# eva01_connectors.net
KiCad netlist of a schematic drawn in Altium Designer
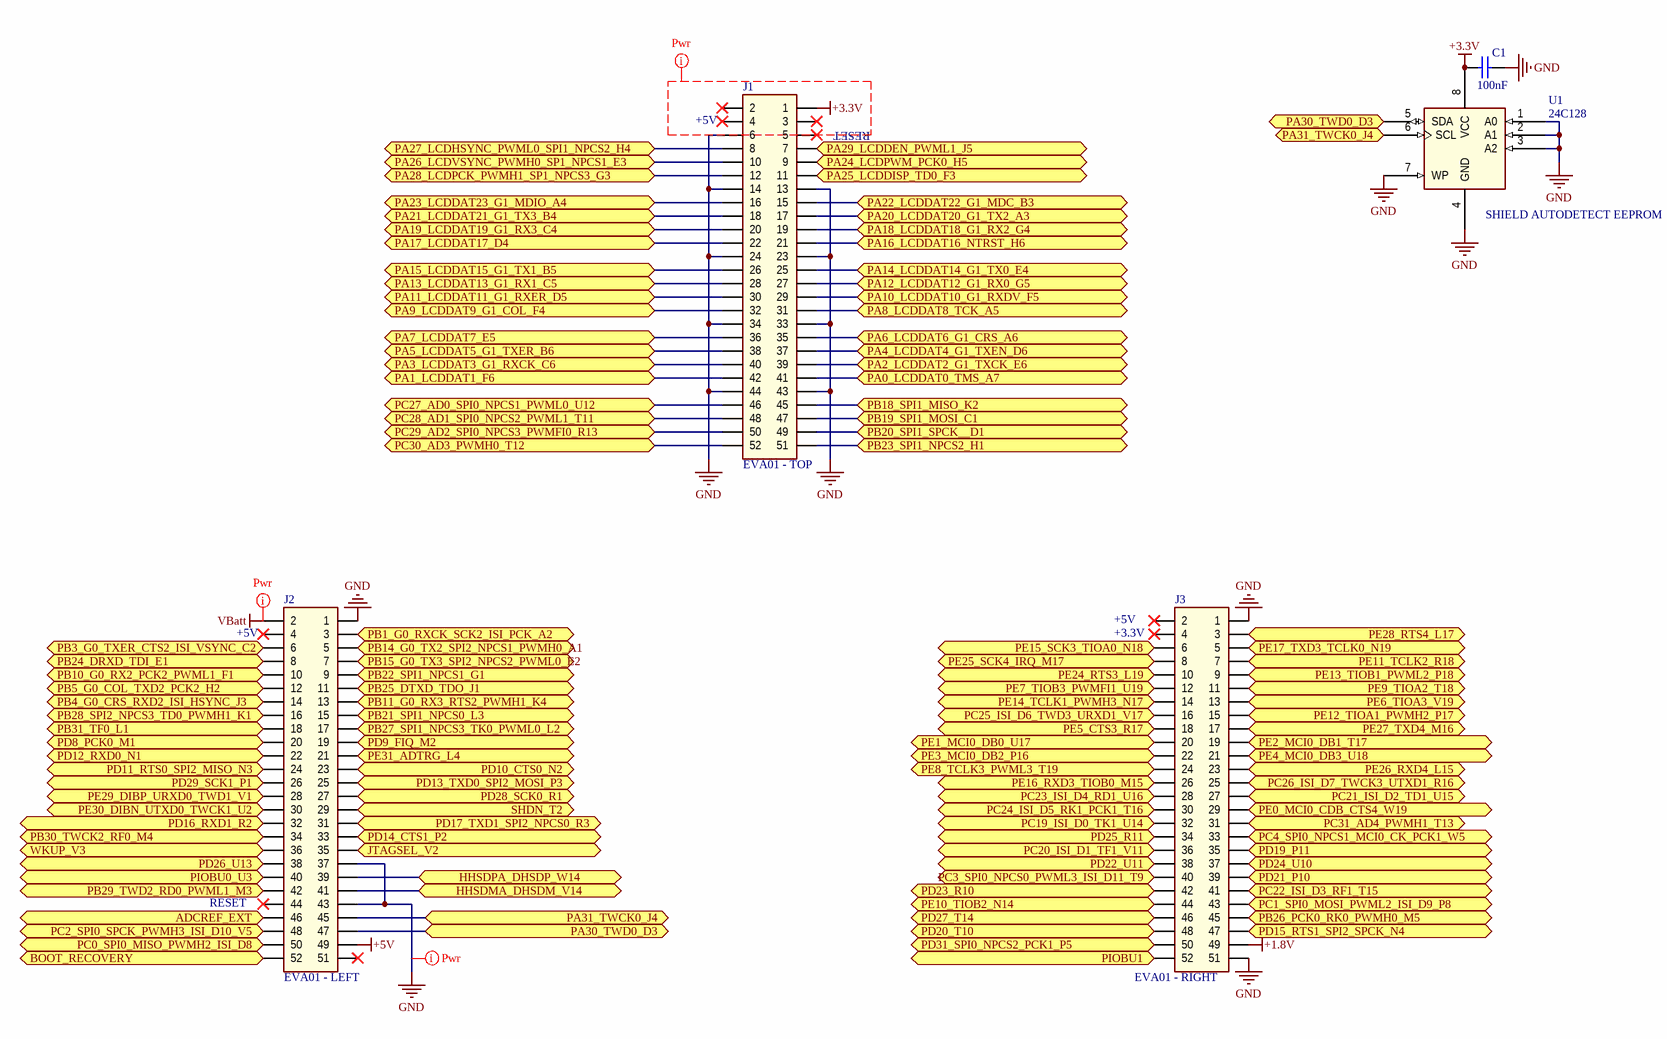
[diagram p0: eva01_connectors.SchDoc]

(export (version "E")
  (design (tool "Eeschema 10.0.6"))
  (components
    (comp (ref "C1")
      (value "100nF")
      (footprint "0603_[1608]")
      (description "Ceramic X7R 50V")
      (fields (field (name "PUBLISHER") "Altium Limited"))
      (libsource (lib "DEVELER_Library") (part "Cap"))
    )
    (comp (ref "J1")
      (value "EVA01 - TOP")
      (footprint "SOCKET_2x26_2.54MM_SMD")
      (description "Socket Header, 26 pin, 13x2, 2.54mm, H=8.5mm")
      (fields (field (name "PART NUMBER") "Tyco 1-1634688"))
      (libsource (lib "DEVELER_Library") (part "Header 26x2"))
    )
    (comp (ref "J2")
      (value "EVA01 - LEFT")
      (footprint "SOCKET_2x26_2.54MM_SMD")
      (description "Pin header 26x2")
      (fields (field (name "PART NUMBER") "Tyco 1-1634688"))
      (libsource (lib "DEVELER_Library") (part "Header 26x2"))
    )
    (comp (ref "J3")
      (value "EVA01 - RIGHT")
      (footprint "SOCKET_2x26_2.54MM_SMD")
      (description "Pin header 26x2")
      (fields (field (name "PART NUMBER") "Tyco 1-1634688"))
      (libsource (lib "DEVELER_Library") (part "Header 26x2"))
    )
    (comp (ref "U1")
      (value "24C128")
      (footprint "SOIC8")
      (description "EEPROM")
      (libsource (lib "DEVELER_Library") (part "EEPROM-SOIC8"))
    )
  )
  (nets
    (net (code "1") (name "+1.8V") (class "Default")
      (node (ref "J3") (pin "49") (pinfunction "49_49") (pintype "passive"))
    )
    (net (code "2") (name "+3.3V") (class "Default")
      (node (ref "C1") (pin "2") (pinfunction "2_2") (pintype "passive"))
      (node (ref "J1") (pin "1") (pinfunction "1_1") (pintype "passive"))
      (node (ref "U1") (pin "8") (pinfunction "VCC_8") (pintype "power_in"))
    )
    (net (code "3") (name "+5V") (class "Default")
      (node (ref "J2") (pin "49") (pinfunction "49_49") (pintype "passive"))
    )
    (net (code "4") (name "/ADCREF_EXT") (class "Default")
      (node (ref "J2") (pin "46") (pinfunction "46_46") (pintype "passive"))
    )
    (net (code "5") (name "/BOOT_RECOVERY") (class "Default")
      (node (ref "J2") (pin "52") (pinfunction "52_52") (pintype "passive"))
    )
    (net (code "6") (name "/HHSDMA_DHSDM_V14") (class "Default")
      (node (ref "J2") (pin "41") (pinfunction "41_41") (pintype "passive"))
    )
    (net (code "7") (name "/HHSDPA_DHSDP_W14") (class "Default")
      (node (ref "J2") (pin "39") (pinfunction "39_39") (pintype "passive"))
    )
    (net (code "8") (name "/JTAGSEL_V2") (class "Default")
      (node (ref "J2") (pin "35") (pinfunction "35_35") (pintype "passive"))
    )
    (net (code "9") (name "/PA0_LCDDAT0_TMS_A7") (class "Default")
      (node (ref "J1") (pin "41") (pinfunction "41_41") (pintype "passive"))
    )
    (net (code "10") (name "/PA1_LCDDAT1_F6") (class "Default")
      (node (ref "J1") (pin "42") (pinfunction "42_42") (pintype "passive"))
    )
    (net (code "11") (name "/PA2_LCDDAT2_G1_TXCK_E6") (class "Default")
      (node (ref "J1") (pin "39") (pinfunction "39_39") (pintype "passive"))
    )
    (net (code "12") (name "/PA3_LCDDAT3_G1_RXCK_C6") (class "Default")
      (node (ref "J1") (pin "40") (pinfunction "40_40") (pintype "passive"))
    )
    (net (code "13") (name "/PA4_LCDDAT4_G1_TXEN_D6") (class "Default")
      (node (ref "J1") (pin "37") (pinfunction "37_37") (pintype "passive"))
    )
    (net (code "14") (name "/PA5_LCDDAT5_G1_TXER_B6") (class "Default")
      (node (ref "J1") (pin "38") (pinfunction "38_38") (pintype "passive"))
    )
    (net (code "15") (name "/PA6_LCDDAT6_G1_CRS_A6") (class "Default")
      (node (ref "J1") (pin "35") (pinfunction "35_35") (pintype "passive"))
    )
    (net (code "16") (name "/PA7_LCDDAT7_E5") (class "Default")
      (node (ref "J1") (pin "36") (pinfunction "36_36") (pintype "passive"))
    )
    (net (code "17") (name "/PA8_LCDDAT8_TCK_A5") (class "Default")
      (node (ref "J1") (pin "31") (pinfunction "31_31") (pintype "passive"))
    )
    (net (code "18") (name "/PA9_LCDDAT9_G1_COL_F4") (class "Default")
      (node (ref "J1") (pin "32") (pinfunction "32_32") (pintype "passive"))
    )
    (net (code "19") (name "/PA10_LCDDAT10_G1_RXDV_F5") (class "Default")
      (node (ref "J1") (pin "29") (pinfunction "29_29") (pintype "passive"))
    )
    (net (code "20") (name "/PA11_LCDDAT11_G1_RXER_D5") (class "Default")
      (node (ref "J1") (pin "30") (pinfunction "30_30") (pintype "passive"))
    )
    (net (code "21") (name "/PA12_LCDDAT12_G1_RX0_G5") (class "Default")
      (node (ref "J1") (pin "27") (pinfunction "27_27") (pintype "passive"))
    )
    (net (code "22") (name "/PA13_LCDDAT13_G1_RX1_C5") (class "Default")
      (node (ref "J1") (pin "28") (pinfunction "28_28") (pintype "passive"))
    )
    (net (code "23") (name "/PA14_LCDDAT14_G1_TX0_E4") (class "Default")
      (node (ref "J1") (pin "25") (pinfunction "25_25") (pintype "passive"))
    )
    (net (code "24") (name "/PA15_LCDDAT15_G1_TX1_B5") (class "Default")
      (node (ref "J1") (pin "26") (pinfunction "26_26") (pintype "passive"))
    )
    (net (code "25") (name "/PA16_LCDDAT16_NTRST_H6") (class "Default")
      (node (ref "J1") (pin "21") (pinfunction "21_21") (pintype "passive"))
    )
    (net (code "26") (name "/PA17_LCDDAT17_D4") (class "Default")
      (node (ref "J1") (pin "22") (pinfunction "22_22") (pintype "passive"))
    )
    (net (code "27") (name "/PA18_LCDDAT18_G1_RX2_G4") (class "Default")
      (node (ref "J1") (pin "19") (pinfunction "19_19") (pintype "passive"))
    )
    (net (code "28") (name "/PA19_LCDDAT19_G1_RX3_C4") (class "Default")
      (node (ref "J1") (pin "20") (pinfunction "20_20") (pintype "passive"))
    )
    (net (code "29") (name "/PA20_LCDDAT20_G1_TX2_A3") (class "Default")
      (node (ref "J1") (pin "17") (pinfunction "17_17") (pintype "passive"))
    )
    (net (code "30") (name "/PA21_LCDDAT21_G1_TX3_B4") (class "Default")
      (node (ref "J1") (pin "18") (pinfunction "18_18") (pintype "passive"))
    )
    (net (code "31") (name "/PA22_LCDDAT22_G1_MDC_B3") (class "Default")
      (node (ref "J1") (pin "15") (pinfunction "15_15") (pintype "passive"))
    )
    (net (code "32") (name "/PA23_LCDDAT23_G1_MDIO_A4") (class "Default")
      (node (ref "J1") (pin "16") (pinfunction "16_16") (pintype "passive"))
    )
    (net (code "33") (name "/PA24_LCDPWM_PCK0_H5") (class "Default")
      (node (ref "J1") (pin "9") (pinfunction "9_9") (pintype "passive"))
    )
    (net (code "34") (name "/PA25_LCDDISP_TD0_F3") (class "Default")
      (node (ref "J1") (pin "11") (pinfunction "11_11") (pintype "passive"))
    )
    (net (code "35") (name "/PA26_LCDVSYNC_PWMH0_SP1_NPCS1_E3") (class "Default")
      (node (ref "J1") (pin "10") (pinfunction "10_10") (pintype "passive"))
    )
    (net (code "36") (name "/PA27_LCDHSYNC_PWML0_SPI1_NPCS2_H4") (class "Default")
      (node (ref "J1") (pin "8") (pinfunction "8_8") (pintype "passive"))
    )
    (net (code "37") (name "/PA28_LCDPCK_PWMH1_SP1_NPCS3_G3") (class "Default")
      (node (ref "J1") (pin "12") (pinfunction "12_12") (pintype "passive"))
    )
    (net (code "38") (name "/PA29_LCDDEN_PWML1_J5") (class "Default")
      (node (ref "J1") (pin "7") (pinfunction "7_7") (pintype "passive"))
    )
    (net (code "39") (name "/PA30_TWD0_D3") (class "Default")
      (node (ref "J2") (pin "47") (pinfunction "47_47") (pintype "passive"))
      (node (ref "U1") (pin "5") (pinfunction "SDA_5") (pintype "bidirectional"))
    )
    (net (code "40") (name "/PA31_TWCK0_J4") (class "Default")
      (node (ref "J2") (pin "45") (pinfunction "45_45") (pintype "passive"))
      (node (ref "U1") (pin "6") (pinfunction "SCL_6") (pintype "input"))
    )
    (net (code "41") (name "/PB1_G0_RXCK_SCK2_ISI_PCK_A2") (class "Default")
      (node (ref "J2") (pin "3") (pinfunction "3_3") (pintype "passive"))
    )
    (net (code "42") (name "/PB3_G0_TXER_CTS2_ISI_VSYNC_C2") (class "Default")
      (node (ref "J2") (pin "6") (pinfunction "6_6") (pintype "passive"))
    )
    (net (code "43") (name "/PB4_G0_CRS_RXD2_ISI_HSYNC_J3") (class "Default")
      (node (ref "J2") (pin "14") (pinfunction "14_14") (pintype "passive"))
    )
    (net (code "44") (name "/PB5_G0_COL_TXD2_PCK2_H2") (class "Default")
      (node (ref "J2") (pin "12") (pinfunction "12_12") (pintype "passive"))
    )
    (net (code "45") (name "/PB10_G0_RX2_PCK2_PWML1_F1") (class "Default")
      (node (ref "J2") (pin "10") (pinfunction "10_10") (pintype "passive"))
    )
    (net (code "46") (name "/PB11_G0_RX3_RTS2_PWMH1_K4") (class "Default")
      (node (ref "J2") (pin "13") (pinfunction "13_13") (pintype "passive"))
    )
    (net (code "47") (name "/PB14_G0_TX2_SPI2_NPCS1_PWMH0_A1") (class "Default")
      (node (ref "J2") (pin "5") (pinfunction "5_5") (pintype "passive"))
    )
    (net (code "48") (name "/PB15_G0_TX3_SPI2_NPCS2_PWML0_E2") (class "Default")
      (node (ref "J2") (pin "7") (pinfunction "7_7") (pintype "passive"))
    )
    (net (code "49") (name "/PB18_SPI1_MISO_K2") (class "Default")
      (node (ref "J1") (pin "45") (pinfunction "45_45") (pintype "passive"))
    )
    (net (code "50") (name "/PB19_SPI1_MOSI_C1") (class "Default")
      (node (ref "J1") (pin "47") (pinfunction "47_47") (pintype "passive"))
    )
    (net (code "51") (name "/PB20_SPI1_SPCK__D1") (class "Default")
      (node (ref "J1") (pin "49") (pinfunction "49_49") (pintype "passive"))
    )
    (net (code "52") (name "/PB21_SPI1_NPCS0_L3") (class "Default")
      (node (ref "J2") (pin "15") (pinfunction "15_15") (pintype "passive"))
    )
    (net (code "53") (name "/PB22_SPI1_NPCS1_G1") (class "Default")
      (node (ref "J2") (pin "9") (pinfunction "9_9") (pintype "passive"))
    )
    (net (code "54") (name "/PB23_SPI1_NPCS2_H1") (class "Default")
      (node (ref "J1") (pin "51") (pinfunction "51_51") (pintype "passive"))
    )
    (net (code "55") (name "/PB24_DRXD_TDI_E1") (class "Default")
      (node (ref "J2") (pin "8") (pinfunction "8_8") (pintype "passive"))
    )
    (net (code "56") (name "/PB25_DTXD_TDO_J1") (class "Default")
      (node (ref "J2") (pin "11") (pinfunction "11_11") (pintype "passive"))
    )
    (net (code "57") (name "/PB26_PCK0_RK0_PWMH0_M5") (class "Default")
      (node (ref "J3") (pin "45") (pinfunction "45_45") (pintype "passive"))
    )
    (net (code "58") (name "/PB27_SPI1_NPCS3_TK0_PWML0_L2") (class "Default")
      (node (ref "J2") (pin "17") (pinfunction "17_17") (pintype "passive"))
    )
    (net (code "59") (name "/PB28_SPI2_NPCS3_TD0_PWMH1_K1") (class "Default")
      (node (ref "J2") (pin "16") (pinfunction "16_16") (pintype "passive"))
    )
    (net (code "60") (name "/PB29_TWD2_RD0_PWML1_M3") (class "Default")
      (node (ref "J2") (pin "42") (pinfunction "42_42") (pintype "passive"))
    )
    (net (code "61") (name "/PB30_TWCK2_RF0_M4") (class "Default")
      (node (ref "J2") (pin "34") (pinfunction "34_34") (pintype "passive"))
    )
    (net (code "62") (name "/PB31_TF0_L1") (class "Default")
      (node (ref "J2") (pin "18") (pinfunction "18_18") (pintype "passive"))
    )
    (net (code "63") (name "/PC0_SPI0_MISO_PWMH2_ISI_D8") (class "Default")
      (node (ref "J2") (pin "50") (pinfunction "50_50") (pintype "passive"))
    )
    (net (code "64") (name "/PC1_SPI0_MOSI_PWML2_ISI_D9_P8") (class "Default")
      (node (ref "J3") (pin "43") (pinfunction "43_43") (pintype "passive"))
    )
    (net (code "65") (name "/PC2_SPI0_SPCK_PWMH3_ISI_D10_V5") (class "Default")
      (node (ref "J2") (pin "48") (pinfunction "48_48") (pintype "passive"))
    )
    (net (code "66") (name "/PC3_SPI0_NPCS0_PWML3_ISI_D11_T9") (class "Default")
      (node (ref "J3") (pin "40") (pinfunction "40_40") (pintype "passive"))
    )
    (net (code "67") (name "/PC4_SPI0_NPCS1_MCI0_CK_PCK1_W5") (class "Default")
      (node (ref "J3") (pin "33") (pinfunction "33_33") (pintype "passive"))
    )
    (net (code "68") (name "/PC19_ISI_D0_TK1_U14") (class "Default")
      (node (ref "J3") (pin "32") (pinfunction "32_32") (pintype "passive"))
    )
    (net (code "69") (name "/PC20_ISI_D1_TF1_V11") (class "Default")
      (node (ref "J3") (pin "36") (pinfunction "36_36") (pintype "passive"))
    )
    (net (code "70") (name "/PC21_ISI_D2_TD1_U15") (class "Default")
      (node (ref "J3") (pin "27") (pinfunction "27_27") (pintype "passive"))
    )
    (net (code "71") (name "/PC22_ISI_D3_RF1_T15") (class "Default")
      (node (ref "J3") (pin "41") (pinfunction "41_41") (pintype "passive"))
    )
    (net (code "72") (name "/PC23_ISI_D4_RD1_U16") (class "Default")
      (node (ref "J3") (pin "28") (pinfunction "28_28") (pintype "passive"))
    )
    (net (code "73") (name "/PC24_ISI_D5_RK1_PCK1_T16") (class "Default")
      (node (ref "J3") (pin "30") (pinfunction "30_30") (pintype "passive"))
    )
    (net (code "74") (name "/PC25_ISI_D6_TWD3_URXD1_V17") (class "Default")
      (node (ref "J3") (pin "16") (pinfunction "16_16") (pintype "passive"))
    )
    (net (code "75") (name "/PC26_ISI_D7_TWCK3_UTXD1_R16") (class "Default")
      (node (ref "J3") (pin "25") (pinfunction "25_25") (pintype "passive"))
    )
    (net (code "76") (name "/PC27_AD0_SPI0_NPCS1_PWML0_U12") (class "Default")
      (node (ref "J1") (pin "46") (pinfunction "46_46") (pintype "passive"))
    )
    (net (code "77") (name "/PC28_AD1_SPI0_NPCS2_PWML1_T11") (class "Default")
      (node (ref "J1") (pin "48") (pinfunction "48_48") (pintype "passive"))
    )
    (net (code "78") (name "/PC29_AD2_SPI0_NPCS3_PWMFI0_R13") (class "Default")
      (node (ref "J1") (pin "50") (pinfunction "50_50") (pintype "passive"))
    )
    (net (code "79") (name "/PC30_AD3_PWMH0_T12") (class "Default")
      (node (ref "J1") (pin "52") (pinfunction "52_52") (pintype "passive"))
    )
    (net (code "80") (name "/PC31_AD4_PWMH1_T13") (class "Default")
      (node (ref "J3") (pin "31") (pinfunction "31_31") (pintype "passive"))
    )
    (net (code "81") (name "/PD8_PCK0_M1") (class "Default")
      (node (ref "J2") (pin "20") (pinfunction "20_20") (pintype "passive"))
    )
    (net (code "82") (name "/PD9_FIQ_M2") (class "Default")
      (node (ref "J2") (pin "19") (pinfunction "19_19") (pintype "passive"))
    )
    (net (code "83") (name "/PD10_CTS0_N2") (class "Default")
      (node (ref "J2") (pin "23") (pinfunction "23_23") (pintype "passive"))
    )
    (net (code "84") (name "/PD11_RTS0_SPI2_MISO_N3") (class "Default")
      (node (ref "J2") (pin "24") (pinfunction "24_24") (pintype "passive"))
    )
    (net (code "85") (name "/PD12_RXD0_N1") (class "Default")
      (node (ref "J2") (pin "22") (pinfunction "22_22") (pintype "passive"))
    )
    (net (code "86") (name "/PD13_TXD0_SPI2_MOSI_P3") (class "Default")
      (node (ref "J2") (pin "25") (pinfunction "25_25") (pintype "passive"))
    )
    (net (code "87") (name "/PD14_CTS1_P2") (class "Default")
      (node (ref "J2") (pin "33") (pinfunction "33_33") (pintype "passive"))
    )
    (net (code "88") (name "/PD15_RTS1_SPI2_SPCK_N4") (class "Default")
      (node (ref "J3") (pin "47") (pinfunction "47_47") (pintype "passive"))
    )
    (net (code "89") (name "/PD16_RXD1_R2") (class "Default")
      (node (ref "J2") (pin "32") (pinfunction "32_32") (pintype "passive"))
    )
    (net (code "90") (name "/PD17_TXD1_SPI2_NPCS0_R3") (class "Default")
      (node (ref "J2") (pin "31") (pinfunction "31_31") (pintype "passive"))
    )
    (net (code "91") (name "/PD19_P11") (class "Default")
      (node (ref "J3") (pin "35") (pinfunction "35_35") (pintype "passive"))
    )
    (net (code "92") (name "/PD20_T10") (class "Default")
      (node (ref "J3") (pin "48") (pinfunction "48_48") (pintype "passive"))
    )
    (net (code "93") (name "/PD21_P10") (class "Default")
      (node (ref "J3") (pin "39") (pinfunction "39_39") (pintype "passive"))
    )
    (net (code "94") (name "/PD22_U11") (class "Default")
      (node (ref "J3") (pin "38") (pinfunction "38_38") (pintype "passive"))
    )
    (net (code "95") (name "/PD23_R10") (class "Default")
      (node (ref "J3") (pin "42") (pinfunction "42_42") (pintype "passive"))
    )
    (net (code "96") (name "/PD24_U10") (class "Default")
      (node (ref "J3") (pin "37") (pinfunction "37_37") (pintype "passive"))
    )
    (net (code "97") (name "/PD25_R11") (class "Default")
      (node (ref "J3") (pin "34") (pinfunction "34_34") (pintype "passive"))
    )
    (net (code "98") (name "/PD26_U13") (class "Default")
      (node (ref "J2") (pin "38") (pinfunction "38_38") (pintype "passive"))
    )
    (net (code "99") (name "/PD27_T14") (class "Default")
      (node (ref "J3") (pin "46") (pinfunction "46_46") (pintype "passive"))
    )
    (net (code "100") (name "/PD28_SCK0_R1") (class "Default")
      (node (ref "J2") (pin "27") (pinfunction "27_27") (pintype "passive"))
    )
    (net (code "101") (name "/PD29_SCK1_P1") (class "Default")
      (node (ref "J2") (pin "26") (pinfunction "26_26") (pintype "passive"))
    )
    (net (code "102") (name "/PD31_SPI0_NPCS2_PCK1_P5") (class "Default")
      (node (ref "J3") (pin "50") (pinfunction "50_50") (pintype "passive"))
    )
    (net (code "103") (name "/PE0_MCI0_CDB_CTS4_W19") (class "Default")
      (node (ref "J3") (pin "29") (pinfunction "29_29") (pintype "passive"))
    )
    (net (code "104") (name "/PE1_MCI0_DB0_U17") (class "Default")
      (node (ref "J3") (pin "20") (pinfunction "20_20") (pintype "passive"))
    )
    (net (code "105") (name "/PE2_MCI0_DB1_T17") (class "Default")
      (node (ref "J3") (pin "19") (pinfunction "19_19") (pintype "passive"))
    )
    (net (code "106") (name "/PE3_MCI0_DB2_P16") (class "Default")
      (node (ref "J3") (pin "22") (pinfunction "22_22") (pintype "passive"))
    )
    (net (code "107") (name "/PE4_MCI0_DB3_U18") (class "Default")
      (node (ref "J3") (pin "21") (pinfunction "21_21") (pintype "passive"))
    )
    (net (code "108") (name "/PE5_CTS3_R17") (class "Default")
      (node (ref "J3") (pin "18") (pinfunction "18_18") (pintype "passive"))
    )
    (net (code "109") (name "/PE6_TIOA3_V19") (class "Default")
      (node (ref "J3") (pin "13") (pinfunction "13_13") (pintype "passive"))
    )
    (net (code "110") (name "/PE7_TIOB3_PWMFI1_U19") (class "Default")
      (node (ref "J3") (pin "12") (pinfunction "12_12") (pintype "passive"))
    )
    (net (code "111") (name "/PE8_TCLK3_PWML3_T19") (class "Default")
      (node (ref "J3") (pin "24") (pinfunction "24_24") (pintype "passive"))
    )
    (net (code "112") (name "/PE9_TIOA2_T18") (class "Default")
      (node (ref "J3") (pin "11") (pinfunction "11_11") (pintype "passive"))
    )
    (net (code "113") (name "/PE10_TIOB2_N14") (class "Default")
      (node (ref "J3") (pin "44") (pinfunction "44_44") (pintype "passive"))
    )
    (net (code "114") (name "/PE11_TCLK2_R18") (class "Default")
      (node (ref "J3") (pin "7") (pinfunction "7_7") (pintype "passive"))
    )
    (net (code "115") (name "/PE12_TIOA1_PWMH2_P17") (class "Default")
      (node (ref "J3") (pin "15") (pinfunction "15_15") (pintype "passive"))
    )
    (net (code "116") (name "/PE13_TIOB1_PWML2_P18") (class "Default")
      (node (ref "J3") (pin "9") (pinfunction "9_9") (pintype "passive"))
    )
    (net (code "117") (name "/PE14_TCLK1_PWMH3_N17") (class "Default")
      (node (ref "J3") (pin "14") (pinfunction "14_14") (pintype "passive"))
    )
    (net (code "118") (name "/PE15_SCK3_TIOA0_N18") (class "Default")
      (node (ref "J3") (pin "6") (pinfunction "6_6") (pintype "passive"))
    )
    (net (code "119") (name "/PE16_RXD3_TIOB0_M15") (class "Default")
      (node (ref "J3") (pin "26") (pinfunction "26_26") (pintype "passive"))
    )
    (net (code "120") (name "/PE17_TXD3_TCLK0_N19") (class "Default")
      (node (ref "J3") (pin "5") (pinfunction "5_5") (pintype "passive"))
    )
    (net (code "121") (name "/PE24_RTS3_L19") (class "Default")
      (node (ref "J3") (pin "10") (pinfunction "10_10") (pintype "passive"))
    )
    (net (code "122") (name "/PE25_SCK4_IRQ_M17") (class "Default")
      (node (ref "J3") (pin "8") (pinfunction "8_8") (pintype "passive"))
    )
    (net (code "123") (name "/PE26_RXD4_L15") (class "Default")
      (node (ref "J3") (pin "23") (pinfunction "23_23") (pintype "passive"))
    )
    (net (code "124") (name "/PE27_TXD4_M16") (class "Default")
      (node (ref "J3") (pin "17") (pinfunction "17_17") (pintype "passive"))
    )
    (net (code "125") (name "/PE28_RTS4_L17") (class "Default")
      (node (ref "J3") (pin "3") (pinfunction "3_3") (pintype "passive"))
    )
    (net (code "126") (name "/PE29_DIBP_URXD0_TWD1_V1") (class "Default")
      (node (ref "J2") (pin "28") (pinfunction "28_28") (pintype "passive"))
    )
    (net (code "127") (name "/PE30_DIBN_UTXD0_TWCK1_U2") (class "Default")
      (node (ref "J2") (pin "30") (pinfunction "30_30") (pintype "passive"))
    )
    (net (code "128") (name "/PE31_ADTRG_L4") (class "Default")
      (node (ref "J2") (pin "21") (pinfunction "21_21") (pintype "passive"))
    )
    (net (code "129") (name "/PIOBU0_U3") (class "Default")
      (node (ref "J2") (pin "40") (pinfunction "40_40") (pintype "passive"))
    )
    (net (code "130") (name "/PIOBU1") (class "Default")
      (node (ref "J3") (pin "52") (pinfunction "52_52") (pintype "passive"))
    )
    (net (code "131") (name "/SHDN_T2") (class "Default")
      (node (ref "J2") (pin "29") (pinfunction "29_29") (pintype "passive"))
    )
    (net (code "132") (name "/WKUP_V3") (class "Default")
      (node (ref "J2") (pin "36") (pinfunction "36_36") (pintype "passive"))
    )
    (net (code "133") (name "GND") (class "Default")
      (node (ref "C1") (pin "1") (pinfunction "1_1") (pintype "passive"))
      (node (ref "J1") (pin "13") (pinfunction "13_13") (pintype "passive"))
      (node (ref "J1") (pin "14") (pinfunction "14_14") (pintype "passive"))
      (node (ref "J1") (pin "23") (pinfunction "23_23") (pintype "passive"))
      (node (ref "J1") (pin "24") (pinfunction "24_24") (pintype "passive"))
      (node (ref "J1") (pin "33") (pinfunction "33_33") (pintype "passive"))
      (node (ref "J1") (pin "34") (pinfunction "34_34") (pintype "passive"))
      (node (ref "J1") (pin "43") (pinfunction "43_43") (pintype "passive"))
      (node (ref "J1") (pin "44") (pinfunction "44_44") (pintype "passive"))
      (node (ref "J1") (pin "6") (pinfunction "6_6") (pintype "passive"))
      (node (ref "J2") (pin "1") (pinfunction "1_1") (pintype "passive"))
      (node (ref "J2") (pin "37") (pinfunction "37_37") (pintype "passive"))
      (node (ref "J2") (pin "43") (pinfunction "43_43") (pintype "passive"))
      (node (ref "J3") (pin "1") (pinfunction "1_1") (pintype "passive"))
      (node (ref "J3") (pin "51") (pinfunction "51_51") (pintype "passive"))
      (node (ref "U1") (pin "1") (pinfunction "A0_1") (pintype "input"))
      (node (ref "U1") (pin "2") (pinfunction "A1_2") (pintype "input"))
      (node (ref "U1") (pin "3") (pinfunction "A2_3") (pintype "input"))
      (node (ref "U1") (pin "4") (pinfunction "GND_4") (pintype "power_in"))
      (node (ref "U1") (pin "7") (pinfunction "WP_7") (pintype "input"))
    )
    (net (code "134") (name "VBatt") (class "Default")
      (node (ref "J2") (pin "2") (pinfunction "2_2") (pintype "passive"))
    )
    (net (code "135") (name "unconnected-(J1-Pad2)") (class "Default")
      (node (ref "J1") (pin "2") (pinfunction "2_2") (pintype "passive+no_connect"))
    )
    (net (code "136") (name "unconnected-(J1-Pad3)") (class "Default")
      (node (ref "J1") (pin "3") (pinfunction "3_3") (pintype "passive+no_connect"))
    )
    (net (code "137") (name "unconnected-(J1-Pad4)") (class "Default")
      (node (ref "J1") (pin "4") (pinfunction "4_4") (pintype "passive+no_connect"))
    )
    (net (code "138") (name "unconnected-(J1-Pad5)") (class "Default")
      (node (ref "J1") (pin "5") (pinfunction "5_5") (pintype "passive+no_connect"))
    )
    (net (code "139") (name "unconnected-(J2-Pad4)") (class "Default")
      (node (ref "J2") (pin "4") (pinfunction "4_4") (pintype "passive+no_connect"))
    )
    (net (code "140") (name "unconnected-(J2-Pad44)") (class "Default")
      (node (ref "J2") (pin "44") (pinfunction "44_44") (pintype "passive+no_connect"))
    )
    (net (code "141") (name "unconnected-(J2-Pad51)") (class "Default")
      (node (ref "J2") (pin "51") (pinfunction "51_51") (pintype "passive+no_connect"))
    )
    (net (code "142") (name "unconnected-(J3-Pad2)") (class "Default")
      (node (ref "J3") (pin "2") (pinfunction "2_2") (pintype "passive+no_connect"))
    )
    (net (code "143") (name "unconnected-(J3-Pad4)") (class "Default")
      (node (ref "J3") (pin "4") (pinfunction "4_4") (pintype "passive+no_connect"))
    )
  )
)
